# motoko_ice_dragon_v2.net
KiCad netlist of a schematic drawn in EAGLE
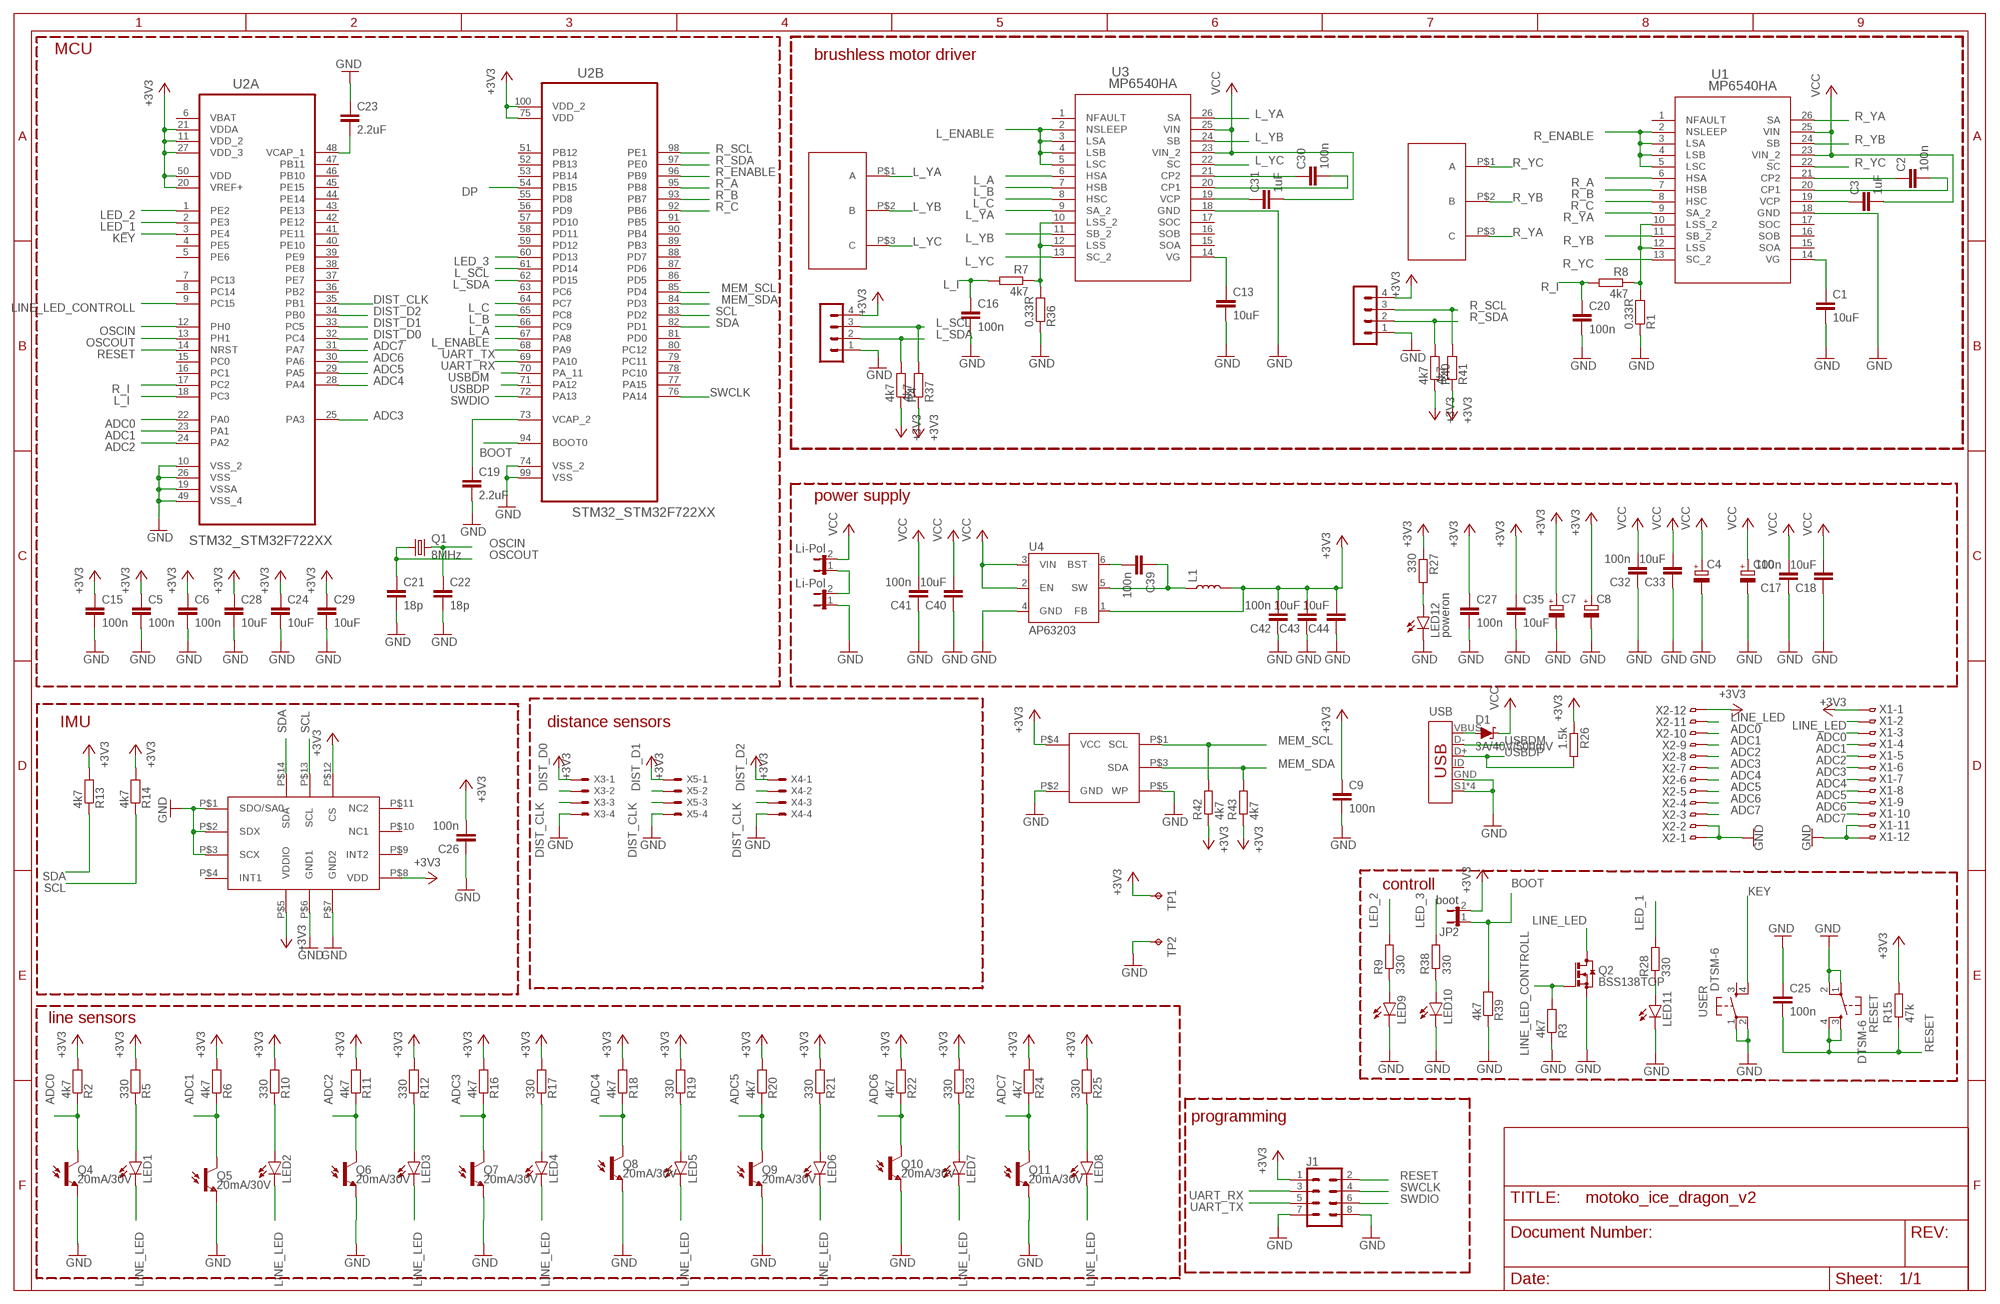
[diagram p0: schematic, sheet 1]

(export (version "E")
  (design (tool "Eeschema 10.0.6"))
  (components
    (comp (ref "C1")
      (value "10uF")
      (footprint "eagle-import:C0805")
      (libsource (lib "eagle-import") (part "C-EUC0805"))
    )
    (comp (ref "C2")
      (value "100n")
      (footprint "eagle-import:C0805")
      (libsource (lib "eagle-import") (part "C-EUC0805"))
    )
    (comp (ref "C3")
      (value "1uF")
      (footprint "eagle-import:C0805")
      (libsource (lib "eagle-import") (part "C-EUC0805"))
    )
    (comp (ref "C4")
      (value "CPOL-EU085CS-1AR")
      (footprint "eagle-import:085CS_1AR")
      (libsource (lib "eagle-import") (part "CPOL-EU085CS-1AR"))
    )
    (comp (ref "C5")
      (value "100n")
      (footprint "eagle-import:C0805")
      (libsource (lib "eagle-import") (part "C-EUC0805"))
    )
    (comp (ref "C6")
      (value "100n")
      (footprint "eagle-import:C0805")
      (libsource (lib "eagle-import") (part "C-EUC0805"))
    )
    (comp (ref "C7")
      (value "CPOL-EU085CS-1AR")
      (footprint "eagle-import:085CS_1AR")
      (libsource (lib "eagle-import") (part "CPOL-EU085CS-1AR"))
    )
    (comp (ref "C8")
      (value "CPOL-EU085CS-1AR")
      (footprint "eagle-import:085CS_1AR")
      (libsource (lib "eagle-import") (part "CPOL-EU085CS-1AR"))
    )
    (comp (ref "C9")
      (value "100n")
      (footprint "eagle-import:C0805")
      (libsource (lib "eagle-import") (part "C-EUC0805"))
    )
    (comp (ref "C10")
      (value "CPOL-EU085CS-1AR")
      (footprint "eagle-import:085CS_1AR")
      (libsource (lib "eagle-import") (part "CPOL-EU085CS-1AR"))
    )
    (comp (ref "C13")
      (value "10uF")
      (footprint "eagle-import:C0805")
      (libsource (lib "eagle-import") (part "C-EUC0805"))
    )
    (comp (ref "C15")
      (value "100n")
      (footprint "eagle-import:C0805")
      (libsource (lib "eagle-import") (part "C-EUC0805"))
    )
    (comp (ref "C16")
      (value "100n")
      (footprint "eagle-import:C0805")
      (libsource (lib "eagle-import") (part "C-EUC0805"))
    )
    (comp (ref "C17")
      (value "100n")
      (footprint "eagle-import:C0805")
      (libsource (lib "eagle-import") (part "C-EUC0805"))
    )
    (comp (ref "C18")
      (value "10uF")
      (footprint "eagle-import:C0805")
      (libsource (lib "eagle-import") (part "C-EUC0805"))
    )
    (comp (ref "C19")
      (value "2.2uF")
      (footprint "eagle-import:C0805")
      (libsource (lib "eagle-import") (part "C-EUC0805"))
    )
    (comp (ref "C20")
      (value "100n")
      (footprint "eagle-import:C0805")
      (libsource (lib "eagle-import") (part "C-EUC0805"))
    )
    (comp (ref "C21")
      (value "18p")
      (footprint "eagle-import:C0805")
      (libsource (lib "eagle-import") (part "C-EUC0805"))
    )
    (comp (ref "C22")
      (value "18p")
      (footprint "eagle-import:C0805")
      (libsource (lib "eagle-import") (part "C-EUC0805"))
    )
    (comp (ref "C23")
      (value "2.2uF")
      (footprint "eagle-import:C0805")
      (libsource (lib "eagle-import") (part "C-EUC0805"))
    )
    (comp (ref "C24")
      (value "10uF")
      (footprint "eagle-import:C0805")
      (libsource (lib "eagle-import") (part "C-EUC0805"))
    )
    (comp (ref "C25")
      (value "100n")
      (footprint "eagle-import:C0805")
      (libsource (lib "eagle-import") (part "C-EUC0805"))
    )
    (comp (ref "C26")
      (value "100n")
      (footprint "eagle-import:C0805")
      (libsource (lib "eagle-import") (part "C-EUC0805"))
    )
    (comp (ref "C27")
      (value "100n")
      (footprint "eagle-import:C0805")
      (libsource (lib "eagle-import") (part "C-EUC0805"))
    )
    (comp (ref "C28")
      (value "10uF")
      (footprint "eagle-import:C0805")
      (libsource (lib "eagle-import") (part "C-EUC0805"))
    )
    (comp (ref "C29")
      (value "10uF")
      (footprint "eagle-import:C0805")
      (libsource (lib "eagle-import") (part "C-EUC0805"))
    )
    (comp (ref "C30")
      (value "100n")
      (footprint "eagle-import:C0805")
      (libsource (lib "eagle-import") (part "C-EUC0805"))
    )
    (comp (ref "C31")
      (value "1uF")
      (footprint "eagle-import:C0805")
      (libsource (lib "eagle-import") (part "C-EUC0805"))
    )
    (comp (ref "C32")
      (value "100n")
      (footprint "eagle-import:C0805")
      (libsource (lib "eagle-import") (part "C-EUC0805"))
    )
    (comp (ref "C33")
      (value "10uF")
      (footprint "eagle-import:C0805")
      (libsource (lib "eagle-import") (part "C-EUC0805"))
    )
    (comp (ref "C35")
      (value "10uF")
      (footprint "eagle-import:C0805")
      (libsource (lib "eagle-import") (part "C-EUC0805"))
    )
    (comp (ref "C39")
      (value "100n")
      (footprint "eagle-import:C0805")
      (libsource (lib "eagle-import") (part "C-EUC0805"))
    )
    (comp (ref "C40")
      (value "10uF")
      (footprint "eagle-import:C0805")
      (libsource (lib "eagle-import") (part "C-EUC0805"))
    )
    (comp (ref "C41")
      (value "100n")
      (footprint "eagle-import:C0805")
      (libsource (lib "eagle-import") (part "C-EUC0805"))
    )
    (comp (ref "C42")
      (value "100n")
      (footprint "eagle-import:C0805")
      (libsource (lib "eagle-import") (part "C-EUC0805"))
    )
    (comp (ref "C43")
      (value "10uF")
      (footprint "eagle-import:C0805")
      (libsource (lib "eagle-import") (part "C-EUC0805"))
    )
    (comp (ref "C44")
      (value "10uF")
      (footprint "eagle-import:C0805")
      (libsource (lib "eagle-import") (part "C-EUC0805"))
    )
    (comp (ref "D1")
      (value "3A/40V/500mV")
      (footprint "eagle-import:SMA-DIODE")
      (libsource (lib "eagle-import") (part "DIODE-SCHOTTKY-B340A"))
    )
    (comp (ref "J1")
      (value "CONN_04X2")
      (footprint "eagle-import:2X4")
      (libsource (lib "eagle-import") (part "CONN_04X2"))
    )
    (comp (ref "JP1")
      (value "Li-Pol")
      (footprint "eagle-import:JP1")
      (libsource (lib "eagle-import") (part "JP1E"))
    )
    (comp (ref "JP2")
      (value "boot")
      (footprint "eagle-import:JP1")
      (libsource (lib "eagle-import") (part "JP1E"))
    )
    (comp (ref "JP3")
      (value "Li-Pol")
      (footprint "eagle-import:JP1")
      (libsource (lib "eagle-import") (part "JP1E"))
    )
    (comp (ref "L1")
      (value "4.7uH, TYS50204R7N-10")
      (footprint "eagle-import:CR54")
      (libsource (lib "eagle-import") (part "INDUCTOR-CR54-3.3UH"))
    )
    (comp (ref "LED1")
      (value "LEDCHIPLED_1206")
      (footprint "eagle-import:CHIPLED_1206")
      (libsource (lib "eagle-import") (part "LEDCHIPLED_1206"))
    )
    (comp (ref "LED2")
      (value "LEDCHIPLED_1206")
      (footprint "eagle-import:CHIPLED_1206")
      (libsource (lib "eagle-import") (part "LEDCHIPLED_1206"))
    )
    (comp (ref "LED3")
      (value "LEDCHIPLED_1206")
      (footprint "eagle-import:CHIPLED_1206")
      (libsource (lib "eagle-import") (part "LEDCHIPLED_1206"))
    )
    (comp (ref "LED4")
      (value "LEDCHIPLED_1206")
      (footprint "eagle-import:CHIPLED_1206")
      (libsource (lib "eagle-import") (part "LEDCHIPLED_1206"))
    )
    (comp (ref "LED5")
      (value "LEDCHIPLED_1206")
      (footprint "eagle-import:CHIPLED_1206")
      (libsource (lib "eagle-import") (part "LEDCHIPLED_1206"))
    )
    (comp (ref "LED6")
      (value "LEDCHIPLED_1206")
      (footprint "eagle-import:CHIPLED_1206")
      (libsource (lib "eagle-import") (part "LEDCHIPLED_1206"))
    )
    (comp (ref "LED7")
      (value "LEDCHIPLED_1206")
      (footprint "eagle-import:CHIPLED_1206")
      (libsource (lib "eagle-import") (part "LEDCHIPLED_1206"))
    )
    (comp (ref "LED8")
      (value "LEDCHIPLED_1206")
      (footprint "eagle-import:CHIPLED_1206")
      (libsource (lib "eagle-import") (part "LEDCHIPLED_1206"))
    )
    (comp (ref "LED9")
      (value "LEDCHIPLED_1206")
      (footprint "eagle-import:CHIPLED_1206")
      (libsource (lib "eagle-import") (part "LEDCHIPLED_1206"))
    )
    (comp (ref "LED10")
      (value "LEDCHIPLED_1206")
      (footprint "eagle-import:CHIPLED_1206")
      (libsource (lib "eagle-import") (part "LEDCHIPLED_1206"))
    )
    (comp (ref "LED11")
      (value "LEDCHIPLED_1206")
      (footprint "eagle-import:CHIPLED_1206")
      (libsource (lib "eagle-import") (part "LEDCHIPLED_1206"))
    )
    (comp (ref "LED12")
      (value "poweron")
      (footprint "eagle-import:CHIPLED_1206")
      (libsource (lib "eagle-import") (part "LEDCHIPLED_1206"))
    )
    (comp (ref "L_ENCODER")
      (value "MA04-1")
      (footprint "eagle-import:MA04-1")
      (libsource (lib "eagle-import") (part "MA04-1"))
    )
    (comp (ref "L_ENCODER1")
      (value "MA04-1")
      (footprint "eagle-import:MA04-1")
      (libsource (lib "eagle-import") (part "MA04-1"))
    )
    (comp (ref "Q1")
      (value "8MHz")
      (footprint "eagle-import:CTS406")
      (libsource (lib "eagle-import") (part "CRYSTALCTS406"))
    )
    (comp (ref "Q2")
      (value "BSS138TOP")
      (footprint "eagle-import:SOT23")
      (libsource (lib "eagle-import") (part "BSS138TOP"))
    )
    (comp (ref "Q4")
      (value "20mA/30V")
      (footprint "eagle-import:PT17-21C-L41-TR8")
      (libsource (lib "eagle-import") (part "PHOTOTRANSISTORPT17-21C-L41-TR8"))
    )
    (comp (ref "Q5")
      (value "20mA/30V")
      (footprint "eagle-import:PT17-21C-L41-TR8")
      (libsource (lib "eagle-import") (part "PHOTOTRANSISTORPT17-21C-L41-TR8"))
    )
    (comp (ref "Q6")
      (value "20mA/30V")
      (footprint "eagle-import:PT17-21C-L41-TR8")
      (libsource (lib "eagle-import") (part "PHOTOTRANSISTORPT17-21C-L41-TR8"))
    )
    (comp (ref "Q7")
      (value "20mA/30V")
      (footprint "eagle-import:PT17-21C-L41-TR8")
      (libsource (lib "eagle-import") (part "PHOTOTRANSISTORPT17-21C-L41-TR8"))
    )
    (comp (ref "Q8")
      (value "20mA/30V")
      (footprint "eagle-import:PT17-21C-L41-TR8")
      (libsource (lib "eagle-import") (part "PHOTOTRANSISTORPT17-21C-L41-TR8"))
    )
    (comp (ref "Q9")
      (value "20mA/30V")
      (footprint "eagle-import:PT17-21C-L41-TR8")
      (libsource (lib "eagle-import") (part "PHOTOTRANSISTORPT17-21C-L41-TR8"))
    )
    (comp (ref "Q10")
      (value "20mA/30V")
      (footprint "eagle-import:PT17-21C-L41-TR8")
      (libsource (lib "eagle-import") (part "PHOTOTRANSISTORPT17-21C-L41-TR8"))
    )
    (comp (ref "Q11")
      (value "20mA/30V")
      (footprint "eagle-import:PT17-21C-L41-TR8")
      (libsource (lib "eagle-import") (part "PHOTOTRANSISTORPT17-21C-L41-TR8"))
    )
    (comp (ref "R1")
      (value "0.33R")
      (footprint "eagle-import:M1206")
      (libsource (lib "eagle-import") (part "R-EU_M1206"))
    )
    (comp (ref "R2")
      (value "4k7")
      (footprint "eagle-import:M0805")
      (libsource (lib "eagle-import") (part "resistor_348_R-EU_M0805"))
    )
    (comp (ref "R3")
      (value "4k7")
      (footprint "eagle-import:M0805")
      (libsource (lib "eagle-import") (part "resistor_348_R-EU_M0805"))
    )
    (comp (ref "R4")
      (value "4k7")
      (footprint "eagle-import:M0805")
      (libsource (lib "eagle-import") (part "resistor_348_R-EU_M0805"))
    )
    (comp (ref "R5")
      (value "330")
      (footprint "eagle-import:M0805")
      (libsource (lib "eagle-import") (part "resistor_348_R-EU_M0805"))
    )
    (comp (ref "R6")
      (value "4k7")
      (footprint "eagle-import:M0805")
      (libsource (lib "eagle-import") (part "resistor_348_R-EU_M0805"))
    )
    (comp (ref "R7")
      (value "4k7")
      (footprint "eagle-import:M0805")
      (libsource (lib "eagle-import") (part "resistor_348_R-EU_M0805"))
    )
    (comp (ref "R8")
      (value "4k7")
      (footprint "eagle-import:M0805")
      (libsource (lib "eagle-import") (part "resistor_348_R-EU_M0805"))
    )
    (comp (ref "R9")
      (value "330")
      (footprint "eagle-import:M0805")
      (libsource (lib "eagle-import") (part "resistor_348_R-EU_M0805"))
    )
    (comp (ref "R10")
      (value "330")
      (footprint "eagle-import:M0805")
      (libsource (lib "eagle-import") (part "resistor_348_R-EU_M0805"))
    )
    (comp (ref "R11")
      (value "4k7")
      (footprint "eagle-import:M0805")
      (libsource (lib "eagle-import") (part "resistor_348_R-EU_M0805"))
    )
    (comp (ref "R12")
      (value "330")
      (footprint "eagle-import:M0805")
      (libsource (lib "eagle-import") (part "resistor_348_R-EU_M0805"))
    )
    (comp (ref "R13")
      (value "4k7")
      (footprint "eagle-import:M0805")
      (libsource (lib "eagle-import") (part "resistor_348_R-EU_M0805"))
    )
    (comp (ref "R14")
      (value "4k7")
      (footprint "eagle-import:M0805")
      (libsource (lib "eagle-import") (part "resistor_348_R-EU_M0805"))
    )
    (comp (ref "R15")
      (value "47k")
      (footprint "eagle-import:M0805")
      (libsource (lib "eagle-import") (part "resistor_348_R-EU_M0805"))
    )
    (comp (ref "R16")
      (value "4k7")
      (footprint "eagle-import:M0805")
      (libsource (lib "eagle-import") (part "resistor_348_R-EU_M0805"))
    )
    (comp (ref "R17")
      (value "330")
      (footprint "eagle-import:M0805")
      (libsource (lib "eagle-import") (part "resistor_348_R-EU_M0805"))
    )
    (comp (ref "R18")
      (value "4k7")
      (footprint "eagle-import:M0805")
      (libsource (lib "eagle-import") (part "resistor_348_R-EU_M0805"))
    )
    (comp (ref "R19")
      (value "330")
      (footprint "eagle-import:M0805")
      (libsource (lib "eagle-import") (part "resistor_348_R-EU_M0805"))
    )
    (comp (ref "R20")
      (value "4k7")
      (footprint "eagle-import:M0805")
      (libsource (lib "eagle-import") (part "resistor_348_R-EU_M0805"))
    )
    (comp (ref "R21")
      (value "330")
      (footprint "eagle-import:M0805")
      (libsource (lib "eagle-import") (part "resistor_348_R-EU_M0805"))
    )
    (comp (ref "R22")
      (value "4k7")
      (footprint "eagle-import:M0805")
      (libsource (lib "eagle-import") (part "resistor_348_R-EU_M0805"))
    )
    (comp (ref "R23")
      (value "330")
      (footprint "eagle-import:M0805")
      (libsource (lib "eagle-import") (part "resistor_348_R-EU_M0805"))
    )
    (comp (ref "R24")
      (value "4k7")
      (footprint "eagle-import:M0805")
      (libsource (lib "eagle-import") (part "resistor_348_R-EU_M0805"))
    )
    (comp (ref "R25")
      (value "330")
      (footprint "eagle-import:M0805")
      (libsource (lib "eagle-import") (part "resistor_348_R-EU_M0805"))
    )
    (comp (ref "R26")
      (value "1.5k")
      (footprint "eagle-import:M0805")
      (libsource (lib "eagle-import") (part "resistor_348_R-EU_M0805"))
    )
    (comp (ref "R27")
      (value "330")
      (footprint "eagle-import:M0805")
      (libsource (lib "eagle-import") (part "resistor_348_R-EU_M0805"))
    )
    (comp (ref "R28")
      (value "330")
      (footprint "eagle-import:M0805")
      (libsource (lib "eagle-import") (part "resistor_348_R-EU_M0805"))
    )
    (comp (ref "R36")
      (value "0.33R")
      (footprint "eagle-import:M1206")
      (libsource (lib "eagle-import") (part "R-EU_M1206"))
    )
    (comp (ref "R37")
      (value "4k7")
      (footprint "eagle-import:M0805")
      (libsource (lib "eagle-import") (part "resistor_348_R-EU_M0805"))
    )
    (comp (ref "R38")
      (value "330")
      (footprint "eagle-import:M0805")
      (libsource (lib "eagle-import") (part "resistor_348_R-EU_M0805"))
    )
    (comp (ref "R39")
      (value "4k7")
      (footprint "eagle-import:M0805")
      (libsource (lib "eagle-import") (part "resistor_348_R-EU_M0805"))
    )
    (comp (ref "R40")
      (value "4k7")
      (footprint "eagle-import:M0805")
      (libsource (lib "eagle-import") (part "resistor_348_R-EU_M0805"))
    )
    (comp (ref "R41")
      (value "4k7")
      (footprint "eagle-import:M0805")
      (libsource (lib "eagle-import") (part "resistor_348_R-EU_M0805"))
    )
    (comp (ref "R42")
      (value "4k7")
      (footprint "eagle-import:M0805")
      (libsource (lib "eagle-import") (part "R-EU_M0805"))
    )
    (comp (ref "R43")
      (value "4k7")
      (footprint "eagle-import:M0805")
      (libsource (lib "eagle-import") (part "R-EU_M0805"))
    )
    (comp (ref "RESET")
      (value "DTSM-6")
      (footprint "eagle-import:DTSM-6")
      (libsource (lib "eagle-import") (part "DTSM-6"))
    )
    (comp (ref "TP1")
      (value "TPB1,27")
      (footprint "eagle-import:B1,27")
      (libsource (lib "eagle-import") (part "TPB1,27"))
    )
    (comp (ref "TP2")
      (value "TPB1,27")
      (footprint "eagle-import:B1,27")
      (libsource (lib "eagle-import") (part "TPB1,27"))
    )
    (comp (ref "U$1")
      (value "BRUSHLESS_GIMBAL_MOTOR_WHEEL")
      (footprint "eagle-import:BRUSHLESS_GIMBAL_MOTOR_WHEEL")
      (libsource (lib "eagle-import") (part "BRUSHLESS_GIMBAL_MOTOR_WHEEL"))
    )
    (comp (ref "U$2")
      (value "BRUSHLESS_GIMBAL_MOTOR_WHEEL")
      (footprint "eagle-import:BRUSHLESS_GIMBAL_MOTOR_WHEEL")
      (libsource (lib "eagle-import") (part "BRUSHLESS_GIMBAL_MOTOR_WHEEL"))
    )
    (comp (ref "U$3")
      (value "LSM6DSM")
      (footprint "eagle-import:LGA14L")
      (libsource (lib "eagle-import") (part "LSM6DSM"))
    )
    (comp (ref "U$4")
      (value "24LC24_SOT23")
      (footprint "eagle-import:SOT23")
      (libsource (lib "eagle-import") (part "24LC24_SOT23"))
    )
    (comp (ref "U1")
      (value "MP6540HA")
      (footprint "eagle-import:QFN-5X5_MP6540HA_MNP")
      (fields (field (name "COPYRIGHT") "Copyright (C) 2018 Accelerated Designs. All rights reserved"))
      (libsource (lib "eagle-import") (part "MP6540HA"))
    )
    (comp (ref "U2")
      (value "STM32_STM32F722XX")
      (footprint "eagle-import:STM32_QFP50P1600X1600X160-100N")
      (fields (field (name "MPN") "STM32F407VET6"))
      (libsource (lib "eagle-import") (part "STM32_STM32F722XX"))
    )
    (comp (ref "U3")
      (value "MP6540HA")
      (footprint "eagle-import:QFN-5X5_MP6540HA_MNP")
      (fields (field (name "COPYRIGHT") "Copyright (C) 2018 Accelerated Designs. All rights reserved"))
      (libsource (lib "eagle-import") (part "MP6540HA"))
    )
    (comp (ref "U4")
      (value "AP63203")
      (footprint "eagle-import:SOT23-6")
      (libsource (lib "eagle-import") (part "AP63203"))
    )
    (comp (ref "USB")
      (value "USB_MINI-B_SMT")
      (footprint "eagle-import:USB-MINIB")
      (libsource (lib "eagle-import") (part "USB_MINI-B_SMT"))
    )
    (comp (ref "USER")
      (value "DTSM-6")
      (footprint "eagle-import:DTSM-6")
      (libsource (lib "eagle-import") (part "DTSM-6"))
    )
    (comp (ref "X1")
      (value "FH12-12S-0.5SH")
      (footprint "eagle-import:FH12-12S-0.5SH")
      (fields (field (name "MPN") "FH12-12S-0.5SH(55)"))
      (libsource (lib "eagle-import") (part "FH12-12S-0.5SH"))
    )
    (comp (ref "X2")
      (value "FH12-12S-0.5SH")
      (footprint "eagle-import:FH12-12S-0.5SH")
      (fields (field (name "MPN") "FH12-12S-0.5SH(55)"))
      (libsource (lib "eagle-import") (part "FH12-12S-0.5SH"))
    )
    (comp (ref "X3")
      (value "52745-0490")
      (footprint "eagle-import:52745-0490")
      (fields (field (name "MF") "MOLEX"))
      (libsource (lib "eagle-import") (part "52745-0490"))
    )
    (comp (ref "X4")
      (value "52745-0490")
      (footprint "eagle-import:52745-0490")
      (fields (field (name "MF") "MOLEX"))
      (libsource (lib "eagle-import") (part "52745-0490"))
    )
    (comp (ref "X5")
      (value "52745-0490")
      (footprint "eagle-import:52745-0490")
      (fields (field (name "MF") "MOLEX"))
      (libsource (lib "eagle-import") (part "52745-0490"))
    )
  )
  (nets
    (net (code "1") (name "+3V3") (class "Default")
      (node (ref "C15") (pin "1") (pinfunction "1_1") (pintype "passive"))
      (node (ref "C24") (pin "1") (pinfunction "1_1") (pintype "passive"))
      (node (ref "C26") (pin "2") (pinfunction "2_2") (pintype "passive"))
      (node (ref "C27") (pin "1") (pinfunction "1_1") (pintype "passive"))
      (node (ref "C28") (pin "1") (pinfunction "1_1") (pintype "passive"))
      (node (ref "C29") (pin "1") (pinfunction "1_1") (pintype "passive"))
      (node (ref "C35") (pin "1") (pinfunction "1_1") (pintype "passive"))
      (node (ref "C42") (pin "2") (pinfunction "2_2") (pintype "passive"))
      (node (ref "C43") (pin "2") (pinfunction "2_2") (pintype "passive"))
      (node (ref "C44") (pin "2") (pinfunction "2_2") (pintype "passive"))
      (node (ref "C5") (pin "1") (pinfunction "1_1") (pintype "passive"))
      (node (ref "C6") (pin "1") (pinfunction "1_1") (pintype "passive"))
      (node (ref "C7") (pin "+") (pinfunction "+_+") (pintype "passive"))
      (node (ref "C8") (pin "+") (pinfunction "+_+") (pintype "passive"))
      (node (ref "C9") (pin "1") (pinfunction "1_1") (pintype "passive"))
      (node (ref "J1") (pin "1") (pinfunction "1_1") (pintype "passive"))
      (node (ref "JP2") (pin "2") (pinfunction "2_2") (pintype "passive"))
      (node (ref "L1") (pin "P$2") (pinfunction "2_P$2") (pintype "passive"))
      (node (ref "L_ENCODER") (pin "4") (pinfunction "4_4") (pintype "passive"))
      (node (ref "L_ENCODER1") (pin "4") (pinfunction "4_4") (pintype "passive"))
      (node (ref "R10") (pin "2") (pinfunction "2_2") (pintype "passive"))
      (node (ref "R11") (pin "2") (pinfunction "2_2") (pintype "passive"))
      (node (ref "R12") (pin "2") (pinfunction "2_2") (pintype "passive"))
      (node (ref "R13") (pin "2") (pinfunction "2_2") (pintype "passive"))
      (node (ref "R14") (pin "2") (pinfunction "2_2") (pintype "passive"))
      (node (ref "R15") (pin "2") (pinfunction "2_2") (pintype "passive"))
      (node (ref "R16") (pin "2") (pinfunction "2_2") (pintype "passive"))
      (node (ref "R17") (pin "2") (pinfunction "2_2") (pintype "passive"))
      (node (ref "R18") (pin "2") (pinfunction "2_2") (pintype "passive"))
      (node (ref "R19") (pin "2") (pinfunction "2_2") (pintype "passive"))
      (node (ref "R2") (pin "2") (pinfunction "2_2") (pintype "passive"))
      (node (ref "R20") (pin "2") (pinfunction "2_2") (pintype "passive"))
      (node (ref "R21") (pin "2") (pinfunction "2_2") (pintype "passive"))
      (node (ref "R22") (pin "2") (pinfunction "2_2") (pintype "passive"))
      (node (ref "R23") (pin "2") (pinfunction "2_2") (pintype "passive"))
      (node (ref "R24") (pin "2") (pinfunction "2_2") (pintype "passive"))
      (node (ref "R25") (pin "2") (pinfunction "2_2") (pintype "passive"))
      (node (ref "R26") (pin "1") (pinfunction "1_1") (pintype "passive"))
      (node (ref "R27") (pin "1") (pinfunction "1_1") (pintype "passive"))
      (node (ref "R37") (pin "1") (pinfunction "1_1") (pintype "passive"))
      (node (ref "R4") (pin "1") (pinfunction "1_1") (pintype "passive"))
      (node (ref "R40") (pin "1") (pinfunction "1_1") (pintype "passive"))
      (node (ref "R41") (pin "1") (pinfunction "1_1") (pintype "passive"))
      (node (ref "R42") (pin "1") (pinfunction "1_1") (pintype "passive"))
      (node (ref "R43") (pin "1") (pinfunction "1_1") (pintype "passive"))
      (node (ref "R5") (pin "2") (pinfunction "2_2") (pintype "passive"))
      (node (ref "R6") (pin "2") (pinfunction "2_2") (pintype "passive"))
      (node (ref "TP1") (pin "TP") (pinfunction "TP_TP") (pintype "input"))
      (node (ref "U$3") (pin "P$12") (pinfunction "CS_P$12") (pintype "bidirectional"))
      (node (ref "U$3") (pin "P$5") (pinfunction "VDDIO_P$5") (pintype "bidirectional"))
      (node (ref "U$3") (pin "P$8") (pinfunction "VDD_P$8") (pintype "bidirectional"))
      (node (ref "U$4") (pin "P$4") (pinfunction "VCC_P$4") (pintype "bidirectional"))
      (node (ref "U2") (pin "100") (pinfunction "VDD_2_100") (pintype "power_in"))
      (node (ref "U2") (pin "11") (pinfunction "VDD_2_11") (pintype "power_in"))
      (node (ref "U2") (pin "20") (pinfunction "VREF+_20") (pintype "power_in"))
      (node (ref "U2") (pin "21") (pinfunction "VDDA_21") (pintype "power_in"))
      (node (ref "U2") (pin "27") (pinfunction "VDD_3_27") (pintype "power_in"))
      (node (ref "U2") (pin "50") (pinfunction "VDD_50") (pintype "power_in"))
      (node (ref "U2") (pin "75") (pinfunction "VDD_75") (pintype "power_in"))
      (node (ref "U4") (pin "1") (pinfunction "FB_1") (pintype "bidirectional"))
      (node (ref "X1") (pin "1") (pinfunction "1_1") (pintype "passive"))
      (node (ref "X2") (pin "12") (pinfunction "1_12") (pintype "passive"))
      (node (ref "X3") (pin "1") (pinfunction "S_1") (pintype "passive"))
      (node (ref "X4") (pin "1") (pinfunction "S_1") (pintype "passive"))
      (node (ref "X5") (pin "1") (pinfunction "S_1") (pintype "passive"))
    )
    (net (code "2") (name "/ADC0") (class "Default")
      (node (ref "Q4") (pin "C") (pinfunction "C_C") (pintype "passive"))
      (node (ref "R2") (pin "1") (pinfunction "1_1") (pintype "passive"))
      (node (ref "U2") (pin "22") (pinfunction "PA0_22") (pintype "bidirectional"))
      (node (ref "X1") (pin "3") (pinfunction "1_3") (pintype "passive"))
      (node (ref "X2") (pin "10") (pinfunction "1_10") (pintype "passive"))
    )
    (net (code "3") (name "/ADC1") (class "Default")
      (node (ref "Q5") (pin "C") (pinfunction "C_C") (pintype "passive"))
      (node (ref "R6") (pin "1") (pinfunction "1_1") (pintype "passive"))
      (node (ref "U2") (pin "23") (pinfunction "PA1_23") (pintype "bidirectional"))
      (node (ref "X1") (pin "4") (pinfunction "1_4") (pintype "passive"))
      (node (ref "X2") (pin "9") (pinfunction "1_9") (pintype "passive"))
    )
    (net (code "4") (name "/ADC2") (class "Default")
      (node (ref "Q6") (pin "C") (pinfunction "C_C") (pintype "passive"))
      (node (ref "R11") (pin "1") (pinfunction "1_1") (pintype "passive"))
      (node (ref "U2") (pin "24") (pinfunction "PA2_24") (pintype "bidirectional"))
      (node (ref "X1") (pin "5") (pinfunction "1_5") (pintype "passive"))
      (node (ref "X2") (pin "8") (pinfunction "1_8") (pintype "passive"))
    )
    (net (code "5") (name "/ADC3") (class "Default")
      (node (ref "Q7") (pin "C") (pinfunction "C_C") (pintype "passive"))
      (node (ref "R16") (pin "1") (pinfunction "1_1") (pintype "passive"))
      (node (ref "U2") (pin "25") (pinfunction "PA3_25") (pintype "bidirectional"))
      (node (ref "X1") (pin "6") (pinfunction "1_6") (pintype "passive"))
      (node (ref "X2") (pin "7") (pinfunction "1_7") (pintype "passive"))
    )
    (net (code "6") (name "/ADC4") (class "Default")
      (node (ref "Q8") (pin "C") (pinfunction "C_C") (pintype "passive"))
      (node (ref "R18") (pin "1") (pinfunction "1_1") (pintype "passive"))
      (node (ref "U2") (pin "28") (pinfunction "PA4_28") (pintype "bidirectional"))
      (node (ref "X1") (pin "7") (pinfunction "1_7") (pintype "passive"))
      (node (ref "X2") (pin "6") (pinfunction "1_6") (pintype "passive"))
    )
    (net (code "7") (name "/ADC5") (class "Default")
      (node (ref "Q9") (pin "C") (pinfunction "C_C") (pintype "passive"))
      (node (ref "R20") (pin "1") (pinfunction "1_1") (pintype "passive"))
      (node (ref "U2") (pin "29") (pinfunction "PA5_29") (pintype "bidirectional"))
      (node (ref "X1") (pin "8") (pinfunction "1_8") (pintype "passive"))
      (node (ref "X2") (pin "5") (pinfunction "1_5") (pintype "passive"))
    )
    (net (code "8") (name "/ADC6") (class "Default")
      (node (ref "Q10") (pin "C") (pinfunction "C_C") (pintype "passive"))
      (node (ref "R22") (pin "1") (pinfunction "1_1") (pintype "passive"))
      (node (ref "U2") (pin "30") (pinfunction "PA6_30") (pintype "bidirectional"))
      (node (ref "X1") (pin "9") (pinfunction "1_9") (pintype "passive"))
      (node (ref "X2") (pin "4") (pinfunction "1_4") (pintype "passive"))
    )
    (net (code "9") (name "/ADC7") (class "Default")
      (node (ref "Q11") (pin "C") (pinfunction "C_C") (pintype "passive"))
      (node (ref "R24") (pin "1") (pinfunction "1_1") (pintype "passive"))
      (node (ref "U2") (pin "31") (pinfunction "PA7_31") (pintype "bidirectional"))
      (node (ref "X1") (pin "10") (pinfunction "1_10") (pintype "passive"))
      (node (ref "X2") (pin "3") (pinfunction "1_3") (pintype "passive"))
    )
    (net (code "10") (name "/BOOT") (class "Default")
      (node (ref "JP2") (pin "1") (pinfunction "1_1") (pintype "passive"))
      (node (ref "R39") (pin "2") (pinfunction "2_2") (pintype "passive"))
      (node (ref "U2") (pin "94") (pinfunction "BOOT0_94") (pintype "input"))
    )
    (net (code "11") (name "/DIST_CLK") (class "Default")
      (node (ref "U2") (pin "35") (pinfunction "PB1_35") (pintype "bidirectional"))
      (node (ref "X3") (pin "3") (pinfunction "S_3") (pintype "passive"))
      (node (ref "X4") (pin "3") (pinfunction "S_3") (pintype "passive"))
      (node (ref "X5") (pin "3") (pinfunction "S_3") (pintype "passive"))
    )
    (net (code "12") (name "/DIST_D0") (class "Default")
      (node (ref "U2") (pin "32") (pinfunction "PC4_32") (pintype "bidirectional"))
      (node (ref "X3") (pin "2") (pinfunction "S_2") (pintype "passive"))
    )
    (net (code "13") (name "/DIST_D1") (class "Default")
      (node (ref "U2") (pin "33") (pinfunction "PC5_33") (pintype "bidirectional"))
      (node (ref "X5") (pin "2") (pinfunction "S_2") (pintype "passive"))
    )
    (net (code "14") (name "/DIST_D2") (class "Default")
      (node (ref "U2") (pin "34") (pinfunction "PB0_34") (pintype "bidirectional"))
      (node (ref "X4") (pin "2") (pinfunction "S_2") (pintype "passive"))
    )
    (net (code "15") (name "/DP") (class "Default")
      (node (ref "U2") (pin "54") (pinfunction "PB15_54") (pintype "bidirectional"))
    )
    (net (code "16") (name "/KEY") (class "Default")
      (node (ref "U2") (pin "3") (pinfunction "PE4_3") (pintype "bidirectional"))
      (node (ref "USER") (pin "4") (pinfunction "4_4") (pintype "passive"))
    )
    (net (code "17") (name "/LED_1") (class "Default")
      (node (ref "R28") (pin "2") (pinfunction "2_2") (pintype "passive"))
      (node (ref "U2") (pin "2") (pinfunction "PE3_2") (pintype "bidirectional"))
    )
    (net (code "18") (name "/LED_2") (class "Default")
      (node (ref "R9") (pin "2") (pinfunction "2_2") (pintype "passive"))
      (node (ref "U2") (pin "1") (pinfunction "PE2_1") (pintype "bidirectional"))
    )
    (net (code "19") (name "/LED_3") (class "Default")
      (node (ref "R38") (pin "2") (pinfunction "2_2") (pintype "passive"))
      (node (ref "U2") (pin "60") (pinfunction "PD13_60") (pintype "bidirectional"))
    )
    (net (code "20") (name "/LINE_LED") (class "Default")
      (node (ref "LED1") (pin "C") (pinfunction "C_C") (pintype "passive"))
      (node (ref "LED2") (pin "C") (pinfunction "C_C") (pintype "passive"))
      (node (ref "LED3") (pin "C") (pinfunction "C_C") (pintype "passive"))
      (node (ref "LED4") (pin "C") (pinfunction "C_C") (pintype "passive"))
      (node (ref "LED5") (pin "C") (pinfunction "C_C") (pintype "passive"))
      (node (ref "LED6") (pin "C") (pinfunction "C_C") (pintype "passive"))
      (node (ref "LED7") (pin "C") (pinfunction "C_C") (pintype "passive"))
      (node (ref "LED8") (pin "C") (pinfunction "C_C") (pintype "passive"))
      (node (ref "Q2") (pin "3") (pinfunction "D_3") (pintype "passive"))
      (node (ref "X1") (pin "2") (pinfunction "1_2") (pintype "passive"))
      (node (ref "X2") (pin "11") (pinfunction "1_11") (pintype "passive"))
    )
    (net (code "21") (name "/LINE_LED_CONTROLL") (class "Default")
      (node (ref "Q2") (pin "1") (pinfunction "G_1") (pintype "passive"))
      (node (ref "R3") (pin "2") (pinfunction "2_2") (pintype "passive"))
      (node (ref "U2") (pin "9") (pinfunction "PC15_9") (pintype "bidirectional"))
    )
    (net (code "22") (name "/L_A") (class "Default")
      (node (ref "U2") (pin "66") (pinfunction "PC9_66") (pintype "bidirectional"))
      (node (ref "U3") (pin "6") (pinfunction "HSA_6") (pintype "passive"))
    )
    (net (code "23") (name "/L_B") (class "Default")
      (node (ref "U2") (pin "65") (pinfunction "PC8_65") (pintype "bidirectional"))
      (node (ref "U3") (pin "7") (pinfunction "HSB_7") (pintype "passive"))
    )
    (net (code "24") (name "/L_C") (class "Default")
      (node (ref "U2") (pin "64") (pinfunction "PC7_64") (pintype "bidirectional"))
      (node (ref "U3") (pin "8") (pinfunction "HSC_8") (pintype "passive"))
    )
    (net (code "25") (name "/L_ENABLE") (class "Default")
      (node (ref "U2") (pin "67") (pinfunction "PA8_67") (pintype "bidirectional"))
      (node (ref "U3") (pin "2") (pinfunction "NSLEEP_2") (pintype "input"))
      (node (ref "U3") (pin "3") (pinfunction "LSA_3") (pintype "passive"))
      (node (ref "U3") (pin "4") (pinfunction "LSB_4") (pintype "passive"))
      (node (ref "U3") (pin "5") (pinfunction "LSC_5") (pintype "passive"))
    )
    (net (code "26") (name "/L_I") (class "Default")
      (node (ref "C16") (pin "1") (pinfunction "1_1") (pintype "passive"))
      (node (ref "R7") (pin "2") (pinfunction "2_2") (pintype "passive"))
      (node (ref "U2") (pin "18") (pinfunction "PC3_18") (pintype "bidirectional"))
    )
    (net (code "27") (name "/L_SCL") (class "Default")
      (node (ref "L_ENCODER") (pin "3") (pinfunction "3_3") (pintype "passive"))
      (node (ref "R37") (pin "2") (pinfunction "2_2") (pintype "passive"))
      (node (ref "U2") (pin "61") (pinfunction "PD14_61") (pintype "bidirectional"))
    )
    (net (code "28") (name "/L_SDA") (class "Default")
      (node (ref "L_ENCODER") (pin "2") (pinfunction "2_2") (pintype "passive"))
      (node (ref "R4") (pin "2") (pinfunction "2_2") (pintype "passive"))
      (node (ref "U2") (pin "62") (pinfunction "PD15_62") (pintype "bidirectional"))
    )
    (net (code "29") (name "/L_YA") (class "Default")
      (node (ref "U$1") (pin "P$1") (pinfunction "A_P$1") (pintype "input"))
      (node (ref "U3") (pin "26") (pinfunction "SA_26") (pintype "output"))
      (node (ref "U3") (pin "9") (pinfunction "SA_2_9") (pintype "output"))
    )
    (net (code "30") (name "/L_YB") (class "Default")
      (node (ref "U$1") (pin "P$2") (pinfunction "B_P$2") (pintype "input"))
      (node (ref "U3") (pin "11") (pinfunction "SB_2_11") (pintype "output"))
      (node (ref "U3") (pin "24") (pinfunction "SB_24") (pintype "output"))
    )
    (net (code "31") (name "/L_YC") (class "Default")
      (node (ref "U$1") (pin "P$3") (pinfunction "C_P$3") (pintype "input"))
      (node (ref "U3") (pin "13") (pinfunction "SC_2_13") (pintype "output"))
      (node (ref "U3") (pin "22") (pinfunction "SC_22") (pintype "output"))
    )
    (net (code "32") (name "/MEM_SCL") (class "Default")
      (node (ref "R42") (pin "2") (pinfunction "2_2") (pintype "passive"))
      (node (ref "U$4") (pin "P$1") (pinfunction "SCL_P$1") (pintype "bidirectional"))
      (node (ref "U2") (pin "85") (pinfunction "PD4_85") (pintype "bidirectional"))
    )
    (net (code "33") (name "/MEM_SDA") (class "Default")
      (node (ref "R43") (pin "2") (pinfunction "2_2") (pintype "passive"))
      (node (ref "U$4") (pin "P$3") (pinfunction "SDA_P$3") (pintype "bidirectional"))
      (node (ref "U2") (pin "84") (pinfunction "PD3_84") (pintype "bidirectional"))
    )
    (net (code "34") (name "/OSCIN") (class "Default")
      (node (ref "C22") (pin "1") (pinfunction "1_1") (pintype "passive"))
      (node (ref "Q1") (pin "3") (pinfunction "2_3") (pintype "passive"))
      (node (ref "U2") (pin "12") (pinfunction "PH0_12") (pintype "bidirectional"))
    )
    (net (code "35") (name "/OSCOUT") (class "Default")
      (node (ref "C21") (pin "1") (pinfunction "1_1") (pintype "passive"))
      (node (ref "Q1") (pin "1") (pinfunction "1_1") (pintype "passive"))
      (node (ref "U2") (pin "13") (pinfunction "PH1_13") (pintype "bidirectional"))
    )
    (net (code "36") (name "/RESET") (class "Default")
      (node (ref "C25") (pin "2") (pinfunction "2_2") (pintype "passive"))
      (node (ref "J1") (pin "2") (pinfunction "2_2") (pintype "passive"))
      (node (ref "R15") (pin "1") (pinfunction "1_1") (pintype "passive"))
      (node (ref "RESET") (pin "3") (pinfunction "3_3") (pintype "passive"))
      (node (ref "RESET") (pin "4") (pinfunction "4_4") (pintype "passive"))
      (node (ref "U2") (pin "14") (pinfunction "NRST_14") (pintype "bidirectional"))
    )
    (net (code "37") (name "/R_A") (class "Default")
      (node (ref "U1") (pin "6") (pinfunction "HSA_6") (pintype "passive"))
      (node (ref "U2") (pin "95") (pinfunction "PB8_95") (pintype "bidirectional"))
    )
    (net (code "38") (name "/R_B") (class "Default")
      (node (ref "U1") (pin "7") (pinfunction "HSB_7") (pintype "passive"))
      (node (ref "U2") (pin "93") (pinfunction "PB7_93") (pintype "bidirectional"))
    )
    (net (code "39") (name "/R_C") (class "Default")
      (node (ref "U1") (pin "8") (pinfunction "HSC_8") (pintype "passive"))
      (node (ref "U2") (pin "92") (pinfunction "PB6_92") (pintype "bidirectional"))
    )
    (net (code "40") (name "/R_ENABLE") (class "Default")
      (node (ref "U1") (pin "2") (pinfunction "NSLEEP_2") (pintype "input"))
      (node (ref "U1") (pin "3") (pinfunction "LSA_3") (pintype "passive"))
      (node (ref "U1") (pin "4") (pinfunction "LSB_4") (pintype "passive"))
      (node (ref "U1") (pin "5") (pinfunction "LSC_5") (pintype "passive"))
      (node (ref "U2") (pin "96") (pinfunction "PB9_96") (pintype "bidirectional"))
    )
    (net (code "41") (name "/R_I") (class "Default")
      (node (ref "C20") (pin "1") (pinfunction "1_1") (pintype "passive"))
      (node (ref "R8") (pin "2") (pinfunction "2_2") (pintype "passive"))
      (node (ref "U2") (pin "17") (pinfunction "PC2_17") (pintype "bidirectional"))
    )
    (net (code "42") (name "/R_SCL") (class "Default")
      (node (ref "L_ENCODER1") (pin "3") (pinfunction "3_3") (pintype "passive"))
      (node (ref "R41") (pin "2") (pinfunction "2_2") (pintype "passive"))
      (node (ref "U2") (pin "98") (pinfunction "PE1_98") (pintype "bidirectional"))
    )
    (net (code "43") (name "/R_SDA") (class "Default")
      (node (ref "L_ENCODER1") (pin "2") (pinfunction "2_2") (pintype "passive"))
      (node (ref "R40") (pin "2") (pinfunction "2_2") (pintype "passive"))
      (node (ref "U2") (pin "97") (pinfunction "PE0_97") (pintype "bidirectional"))
    )
    (net (code "44") (name "/R_YA") (class "Default")
      (node (ref "U$2") (pin "P$3") (pinfunction "C_P$3") (pintype "input"))
      (node (ref "U1") (pin "26") (pinfunction "SA_26") (pintype "output"))
      (node (ref "U1") (pin "9") (pinfunction "SA_2_9") (pintype "output"))
    )
    (net (code "45") (name "/R_YB") (class "Default")
      (node (ref "U$2") (pin "P$2") (pinfunction "B_P$2") (pintype "input"))
      (node (ref "U1") (pin "11") (pinfunction "SB_2_11") (pintype "output"))
      (node (ref "U1") (pin "24") (pinfunction "SB_24") (pintype "output"))
    )
    (net (code "46") (name "/R_YC") (class "Default")
      (node (ref "U$2") (pin "P$1") (pinfunction "A_P$1") (pintype "input"))
      (node (ref "U1") (pin "13") (pinfunction "SC_2_13") (pintype "output"))
      (node (ref "U1") (pin "22") (pinfunction "SC_22") (pintype "output"))
    )
    (net (code "47") (name "/SCL") (class "Default")
      (node (ref "R14") (pin "1") (pinfunction "1_1") (pintype "passive"))
      (node (ref "U$3") (pin "P$13") (pinfunction "SCL_P$13") (pintype "bidirectional"))
      (node (ref "U2") (pin "83") (pinfunction "PD2_83") (pintype "bidirectional"))
    )
    (net (code "48") (name "/SDA") (class "Default")
      (node (ref "R13") (pin "1") (pinfunction "1_1") (pintype "passive"))
      (node (ref "U$3") (pin "P$14") (pinfunction "SDA_P$14") (pintype "bidirectional"))
      (node (ref "U2") (pin "82") (pinfunction "PD1_82") (pintype "bidirectional"))
    )
    (net (code "49") (name "/SWCLK") (class "Default")
      (node (ref "J1") (pin "4") (pinfunction "4_4") (pintype "passive"))
      (node (ref "U2") (pin "76") (pinfunction "PA14_76") (pintype "bidirectional"))
    )
    (net (code "50") (name "/SWDIO") (class "Default")
      (node (ref "J1") (pin "6") (pinfunction "6_6") (pintype "passive"))
      (node (ref "U2") (pin "72") (pinfunction "PA13_72") (pintype "bidirectional"))
    )
    (net (code "51") (name "/UART_RX") (class "Default")
      (node (ref "J1") (pin "3") (pinfunction "3_3") (pintype "passive"))
      (node (ref "U2") (pin "69") (pinfunction "PA10_69") (pintype "bidirectional"))
    )
    (net (code "52") (name "/UART_TX") (class "Default")
      (node (ref "J1") (pin "5") (pinfunction "5_5") (pintype "passive"))
      (node (ref "U2") (pin "68") (pinfunction "PA9_68") (pintype "bidirectional"))
    )
    (net (code "53") (name "/USBDM") (class "Default")
      (node (ref "U2") (pin "70") (pinfunction "PA_11_70") (pintype "bidirectional"))
      (node (ref "USB") (pin "D-") (pinfunction "D-_D-") (pintype "bidirectional"))
    )
    (net (code "54") (name "/USBDP") (class "Default")
      (node (ref "R26") (pin "2") (pinfunction "2_2") (pintype "passive"))
      (node (ref "U2") (pin "71") (pinfunction "PA12_71") (pintype "bidirectional"))
      (node (ref "USB") (pin "D+") (pinfunction "D+_D+") (pintype "bidirectional"))
    )
    (net (code "55") (name "/VBAT") (class "Default")
      (node (ref "U2") (pin "6") (pinfunction "VBAT_6") (pintype "power_in"))
    )
    (net (code "56") (name "GND") (class "Default")
      (node (ref "C1") (pin "2") (pinfunction "2_2") (pintype "passive"))
      (node (ref "C10") (pin "-") (pinfunction "-_-") (pintype "passive"))
      (node (ref "C13") (pin "2") (pinfunction "2_2") (pintype "passive"))
      (node (ref "C15") (pin "2") (pinfunction "2_2") (pintype "passive"))
      (node (ref "C16") (pin "2") (pinfunction "2_2") (pintype "passive"))
      (node (ref "C17") (pin "1") (pinfunction "1_1") (pintype "passive"))
      (node (ref "C18") (pin "1") (pinfunction "1_1") (pintype "passive"))
      (node (ref "C19") (pin "2") (pinfunction "2_2") (pintype "passive"))
      (node (ref "C20") (pin "2") (pinfunction "2_2") (pintype "passive"))
      (node (ref "C21") (pin "2") (pinfunction "2_2") (pintype "passive"))
      (node (ref "C22") (pin "2") (pinfunction "2_2") (pintype "passive"))
      (node (ref "C23") (pin "1") (pinfunction "1_1") (pintype "passive"))
      (node (ref "C24") (pin "2") (pinfunction "2_2") (pintype "passive"))
      (node (ref "C25") (pin "1") (pinfunction "1_1") (pintype "passive"))
      (node (ref "C26") (pin "1") (pinfunction "1_1") (pintype "passive"))
      (node (ref "C27") (pin "2") (pinfunction "2_2") (pintype "passive"))
      (node (ref "C28") (pin "2") (pinfunction "2_2") (pintype "passive"))
      (node (ref "C29") (pin "2") (pinfunction "2_2") (pintype "passive"))
      (node (ref "C32") (pin "1") (pinfunction "1_1") (pintype "passive"))
      (node (ref "C33") (pin "1") (pinfunction "1_1") (pintype "passive"))
      (node (ref "C35") (pin "2") (pinfunction "2_2") (pintype "passive"))
      (node (ref "C4") (pin "-") (pinfunction "-_-") (pintype "passive"))
      (node (ref "C40") (pin "1") (pinfunction "1_1") (pintype "passive"))
      (node (ref "C41") (pin "1") (pinfunction "1_1") (pintype "passive"))
      (node (ref "C42") (pin "1") (pinfunction "1_1") (pintype "passive"))
      (node (ref "C43") (pin "1") (pinfunction "1_1") (pintype "passive"))
      (node (ref "C44") (pin "1") (pinfunction "1_1") (pintype "passive"))
      (node (ref "C5") (pin "2") (pinfunction "2_2") (pintype "passive"))
      (node (ref "C6") (pin "2") (pinfunction "2_2") (pintype "passive"))
      (node (ref "C7") (pin "-") (pinfunction "-_-") (pintype "passive"))
      (node (ref "C8") (pin "-") (pinfunction "-_-") (pintype "passive"))
      (node (ref "C9") (pin "2") (pinfunction "2_2") (pintype "passive"))
      (node (ref "J1") (pin "7") (pinfunction "7_7") (pintype "passive"))
      (node (ref "J1") (pin "8") (pinfunction "8_8") (pintype "passive"))
      (node (ref "JP3") (pin "1") (pinfunction "1_1") (pintype "passive"))
      (node (ref "LED10") (pin "C") (pinfunction "C_C") (pintype "passive"))
      (node (ref "LED11") (pin "C") (pinfunction "C_C") (pintype "passive"))
      (node (ref "LED12") (pin "C") (pinfunction "C_C") (pintype "passive"))
      (node (ref "LED9") (pin "C") (pinfunction "C_C") (pintype "passive"))
      (node (ref "L_ENCODER") (pin "1") (pinfunction "1_1") (pintype "passive"))
      (node (ref "L_ENCODER1") (pin "1") (pinfunction "1_1") (pintype "passive"))
      (node (ref "Q10") (pin "E") (pinfunction "E_E") (pintype "passive"))
      (node (ref "Q11") (pin "E") (pinfunction "E_E") (pintype "passive"))
      (node (ref "Q2") (pin "2") (pinfunction "S_2") (pintype "passive"))
      (node (ref "Q4") (pin "E") (pinfunction "E_E") (pintype "passive"))
      (node (ref "Q5") (pin "E") (pinfunction "E_E") (pintype "passive"))
      (node (ref "Q6") (pin "E") (pinfunction "E_E") (pintype "passive"))
      (node (ref "Q7") (pin "E") (pinfunction "E_E") (pintype "passive"))
      (node (ref "Q8") (pin "E") (pinfunction "E_E") (pintype "passive"))
      (node (ref "Q9") (pin "E") (pinfunction "E_E") (pintype "passive"))
      (node (ref "R1") (pin "1") (pinfunction "1_1") (pintype "passive"))
      (node (ref "R3") (pin "1") (pinfunction "1_1") (pintype "passive"))
      (node (ref "R36") (pin "1") (pinfunction "1_1") (pintype "passive"))
      (node (ref "R39") (pin "1") (pinfunction "1_1") (pintype "passive"))
      (node (ref "RESET") (pin "1") (pinfunction "1_1") (pintype "passive"))
      (node (ref "RESET") (pin "2") (pinfunction "2_2") (pintype "passive"))
      (node (ref "TP2") (pin "TP") (pinfunction "TP_TP") (pintype "input"))
      (node (ref "U$3") (pin "P$1") (pinfunction "SDO/SA0_P$1") (pintype "bidirectional"))
      (node (ref "U$3") (pin "P$2") (pinfunction "SDX_P$2") (pintype "bidirectional"))
      (node (ref "U$3") (pin "P$3") (pinfunction "SCX_P$3") (pintype "bidirectional"))
      (node (ref "U$3") (pin "P$6") (pinfunction "GND1_P$6") (pintype "bidirectional"))
      (node (ref "U$3") (pin "P$7") (pinfunction "GND2_P$7") (pintype "bidirectional"))
      (node (ref "U$4") (pin "P$2") (pinfunction "GND_P$2") (pintype "bidirectional"))
      (node (ref "U$4") (pin "P$5") (pinfunction "WP_P$5") (pintype "bidirectional"))
      (node (ref "U1") (pin "18") (pinfunction "GND_18") (pintype "passive"))
      (node (ref "U2") (pin "10") (pinfunction "VSS_2_10") (pintype "passive"))
      (node (ref "U2") (pin "19") (pinfunction "VSSA_19") (pintype "passive"))
      (node (ref "U2") (pin "26") (pinfunction "VSS_26") (pintype "passive"))
      (node (ref "U2") (pin "49") (pinfunction "VSS_4_49") (pintype "power_in"))
      (node (ref "U2") (pin "74") (pinfunction "VSS_2_74") (pintype "passive"))
      (node (ref "U2") (pin "99") (pinfunction "VSS_99") (pintype "passive"))
      (node (ref "U3") (pin "18") (pinfunction "GND_18") (pintype "passive"))
      (node (ref "U4") (pin "4") (pinfunction "GND_4") (pintype "bidirectional"))
      (node (ref "USB") (pin "GND") (pinfunction "GND_GND") (pintype "power_in"))
      (node (ref "USB") (pin "S1") (pinfunction "SHIELD_S1") (pintype "bidirectional"))
      (node (ref "USB") (pin "S2") (pinfunction "SHIELD_S2") (pintype "bidirectional"))
      (node (ref "USB") (pin "S3") (pinfunction "SHIELD_S3") (pintype "bidirectional"))
      (node (ref "USB") (pin "S4") (pinfunction "SHIELD_S4") (pintype "bidirectional"))
      (node (ref "USER") (pin "1") (pinfunction "1_1") (pintype "passive"))
      (node (ref "USER") (pin "2") (pinfunction "2_2") (pintype "passive"))
      (node (ref "X1") (pin "11") (pinfunction "1_11") (pintype "passive"))
      (node (ref "X1") (pin "12") (pinfunction "1_12") (pintype "passive"))
      (node (ref "X2") (pin "1") (pinfunction "1_1") (pintype "passive"))
      (node (ref "X2") (pin "2") (pinfunction "1_2") (pintype "passive"))
      (node (ref "X3") (pin "4") (pinfunction "S_4") (pintype "passive"))
      (node (ref "X4") (pin "4") (pinfunction "S_4") (pintype "passive"))
      (node (ref "X5") (pin "4") (pinfunction "S_4") (pintype "passive"))
    )
    (net (code "57") (name "Net-(D1-PadA)") (class "Default")
      (node (ref "D1") (pin "A") (pinfunction "A_A") (pintype "passive"))
      (node (ref "USB") (pin "VBUS") (pinfunction "VBUS_VBUS") (pintype "power_in"))
    )
    (net (code "58") (name "Net-(JP1-Pad1)") (class "Default")
      (node (ref "JP1") (pin "1") (pinfunction "1_1") (pintype "passive"))
      (node (ref "JP3") (pin "2") (pinfunction "2_2") (pintype "passive"))
    )
    (net (code "59") (name "Net-(L1-1)") (class "Default")
      (node (ref "C39") (pin "1") (pinfunction "1_1") (pintype "passive"))
      (node (ref "L1") (pin "P$1") (pinfunction "1_P$1") (pintype "passive"))
      (node (ref "U4") (pin "5") (pinfunction "SW_5") (pintype "bidirectional"))
    )
    (net (code "60") (name "Net-(LED1-PadA)") (class "Default")
      (node (ref "LED1") (pin "A") (pinfunction "A_A") (pintype "passive"))
      (node (ref "R5") (pin "1") (pinfunction "1_1") (pintype "passive"))
    )
    (net (code "61") (name "Net-(LED2-PadA)") (class "Default")
      (node (ref "LED2") (pin "A") (pinfunction "A_A") (pintype "passive"))
      (node (ref "R10") (pin "1") (pinfunction "1_1") (pintype "passive"))
    )
    (net (code "62") (name "Net-(LED3-PadA)") (class "Default")
      (node (ref "LED3") (pin "A") (pinfunction "A_A") (pintype "passive"))
      (node (ref "R12") (pin "1") (pinfunction "1_1") (pintype "passive"))
    )
    (net (code "63") (name "Net-(LED4-PadA)") (class "Default")
      (node (ref "LED4") (pin "A") (pinfunction "A_A") (pintype "passive"))
      (node (ref "R17") (pin "1") (pinfunction "1_1") (pintype "passive"))
    )
    (net (code "64") (name "Net-(LED5-PadA)") (class "Default")
      (node (ref "LED5") (pin "A") (pinfunction "A_A") (pintype "passive"))
      (node (ref "R19") (pin "1") (pinfunction "1_1") (pintype "passive"))
    )
    (net (code "65") (name "Net-(LED6-PadA)") (class "Default")
      (node (ref "LED6") (pin "A") (pinfunction "A_A") (pintype "passive"))
      (node (ref "R21") (pin "1") (pinfunction "1_1") (pintype "passive"))
    )
    (net (code "66") (name "Net-(LED7-PadA)") (class "Default")
      (node (ref "LED7") (pin "A") (pinfunction "A_A") (pintype "passive"))
      (node (ref "R23") (pin "1") (pinfunction "1_1") (pintype "passive"))
    )
    (net (code "67") (name "Net-(LED8-PadA)") (class "Default")
      (node (ref "LED8") (pin "A") (pinfunction "A_A") (pintype "passive"))
      (node (ref "R25") (pin "1") (pinfunction "1_1") (pintype "passive"))
    )
    (net (code "68") (name "Net-(LED9-PadA)") (class "Default")
      (node (ref "LED9") (pin "A") (pinfunction "A_A") (pintype "passive"))
      (node (ref "R9") (pin "1") (pinfunction "1_1") (pintype "passive"))
    )
    (net (code "69") (name "Net-(LED10-PadA)") (class "Default")
      (node (ref "LED10") (pin "A") (pinfunction "A_A") (pintype "passive"))
      (node (ref "R38") (pin "1") (pinfunction "1_1") (pintype "passive"))
    )
    (net (code "70") (name "Net-(LED11-PadA)") (class "Default")
      (node (ref "LED11") (pin "A") (pinfunction "A_A") (pintype "passive"))
      (node (ref "R28") (pin "1") (pinfunction "1_1") (pintype "passive"))
    )
    (net (code "71") (name "Net-(LED12-PadA)") (class "Default")
      (node (ref "LED12") (pin "A") (pinfunction "A_A") (pintype "passive"))
      (node (ref "R27") (pin "2") (pinfunction "2_2") (pintype "passive"))
    )
    (net (code "72") (name "Net-(U1-CP1)") (class "Default")
      (node (ref "C2") (pin "2") (pinfunction "2_2") (pintype "passive"))
      (node (ref "U1") (pin "20") (pinfunction "CP1_20") (pintype "passive"))
    )
    (net (code "73") (name "Net-(U1-CP2)") (class "Default")
      (node (ref "C2") (pin "1") (pinfunction "1_1") (pintype "passive"))
      (node (ref "U1") (pin "21") (pinfunction "CP2_21") (pintype "passive"))
    )
    (net (code "74") (name "Net-(U1-LSS)") (class "Default")
      (node (ref "R1") (pin "2") (pinfunction "2_2") (pintype "passive"))
      (node (ref "R8") (pin "1") (pinfunction "1_1") (pintype "passive"))
      (node (ref "U1") (pin "10") (pinfunction "LSS_2_10") (pintype "passive"))
      (node (ref "U1") (pin "12") (pinfunction "LSS_12") (pintype "passive"))
    )
    (net (code "75") (name "Net-(U1-VCP)") (class "Default")
      (node (ref "C3") (pin "1") (pinfunction "1_1") (pintype "passive"))
      (node (ref "U1") (pin "19") (pinfunction "VCP_19") (pintype "output"))
    )
    (net (code "76") (name "Net-(U1-VG)") (class "Default")
      (node (ref "C1") (pin "1") (pinfunction "1_1") (pintype "passive"))
      (node (ref "U1") (pin "14") (pinfunction "VG_14") (pintype "power_in"))
    )
    (net (code "77") (name "Net-(U2A-VCAP_1)") (class "Default")
      (node (ref "C23") (pin "2") (pinfunction "2_2") (pintype "passive"))
      (node (ref "U2") (pin "48") (pinfunction "VCAP_1_48") (pintype "power_in"))
    )
    (net (code "78") (name "Net-(U2B-VCAP_2)") (class "Default")
      (node (ref "C19") (pin "1") (pinfunction "1_1") (pintype "passive"))
      (node (ref "U2") (pin "73") (pinfunction "VCAP_2_73") (pintype "power_in"))
    )
    (net (code "79") (name "Net-(U3-CP1)") (class "Default")
      (node (ref "C30") (pin "2") (pinfunction "2_2") (pintype "passive"))
      (node (ref "U3") (pin "20") (pinfunction "CP1_20") (pintype "passive"))
    )
    (net (code "80") (name "Net-(U3-CP2)") (class "Default")
      (node (ref "C30") (pin "1") (pinfunction "1_1") (pintype "passive"))
      (node (ref "U3") (pin "21") (pinfunction "CP2_21") (pintype "passive"))
    )
    (net (code "81") (name "Net-(U3-LSS)") (class "Default")
      (node (ref "R36") (pin "2") (pinfunction "2_2") (pintype "passive"))
      (node (ref "R7") (pin "1") (pinfunction "1_1") (pintype "passive"))
      (node (ref "U3") (pin "10") (pinfunction "LSS_2_10") (pintype "passive"))
      (node (ref "U3") (pin "12") (pinfunction "LSS_12") (pintype "passive"))
    )
    (net (code "82") (name "Net-(U3-VCP)") (class "Default")
      (node (ref "C31") (pin "1") (pinfunction "1_1") (pintype "passive"))
      (node (ref "U3") (pin "19") (pinfunction "VCP_19") (pintype "output"))
    )
    (net (code "83") (name "Net-(U3-VG)") (class "Default")
      (node (ref "C13") (pin "1") (pinfunction "1_1") (pintype "passive"))
      (node (ref "U3") (pin "14") (pinfunction "VG_14") (pintype "power_in"))
    )
    (net (code "84") (name "Net-(U4-BST)") (class "Default")
      (node (ref "C39") (pin "2") (pinfunction "2_2") (pintype "passive"))
      (node (ref "U4") (pin "6") (pinfunction "BST_6") (pintype "bidirectional"))
    )
    (net (code "85") (name "VCC") (class "Default")
      (node (ref "C10") (pin "+") (pinfunction "+_+") (pintype "passive"))
      (node (ref "C17") (pin "2") (pinfunction "2_2") (pintype "passive"))
      (node (ref "C18") (pin "2") (pinfunction "2_2") (pintype "passive"))
      (node (ref "C3") (pin "2") (pinfunction "2_2") (pintype "passive"))
      (node (ref "C31") (pin "2") (pinfunction "2_2") (pintype "passive"))
      (node (ref "C32") (pin "2") (pinfunction "2_2") (pintype "passive"))
      (node (ref "C33") (pin "2") (pinfunction "2_2") (pintype "passive"))
      (node (ref "C4") (pin "+") (pinfunction "+_+") (pintype "passive"))
      (node (ref "C40") (pin "2") (pinfunction "2_2") (pintype "passive"))
      (node (ref "C41") (pin "2") (pinfunction "2_2") (pintype "passive"))
      (node (ref "D1") (pin "C") (pinfunction "C_C") (pintype "passive"))
      (node (ref "JP1") (pin "2") (pinfunction "2_2") (pintype "passive"))
      (node (ref "U1") (pin "23") (pinfunction "VIN_2_23") (pintype "power_in"))
      (node (ref "U1") (pin "25") (pinfunction "VIN_25") (pintype "power_in"))
      (node (ref "U3") (pin "23") (pinfunction "VIN_2_23") (pintype "power_in"))
      (node (ref "U3") (pin "25") (pinfunction "VIN_25") (pintype "power_in"))
      (node (ref "U4") (pin "2") (pinfunction "EN_2") (pintype "bidirectional"))
      (node (ref "U4") (pin "3") (pinfunction "VIN_3") (pintype "bidirectional"))
    )
    (net (code "86") (name "unconnected-(U$3-INT1-PadP$4)") (class "Default")
      (node (ref "U$3") (pin "P$4") (pinfunction "INT1_P$4") (pintype "bidirectional"))
    )
    (net (code "87") (name "unconnected-(U$3-INT2-PadP$9)") (class "Default")
      (node (ref "U$3") (pin "P$9") (pinfunction "INT2_P$9") (pintype "bidirectional"))
    )
    (net (code "88") (name "unconnected-(U$3-NC1-PadP$10)") (class "Default")
      (node (ref "U$3") (pin "P$10") (pinfunction "NC1_P$10") (pintype "bidirectional"))
    )
    (net (code "89") (name "unconnected-(U$3-NC2-PadP$11)") (class "Default")
      (node (ref "U$3") (pin "P$11") (pinfunction "NC2_P$11") (pintype "bidirectional"))
    )
    (net (code "90") (name "unconnected-(U1-NFAULT-Pad1)") (class "Default")
      (node (ref "U1") (pin "1") (pinfunction "NFAULT_1") (pintype "output"))
    )
    (net (code "91") (name "unconnected-(U1-SOA-Pad15)") (class "Default")
      (node (ref "U1") (pin "15") (pinfunction "SOA_15") (pintype "output"))
    )
    (net (code "92") (name "unconnected-(U1-SOB-Pad16)") (class "Default")
      (node (ref "U1") (pin "16") (pinfunction "SOB_16") (pintype "output"))
    )
    (net (code "93") (name "unconnected-(U1-SOC-Pad17)") (class "Default")
      (node (ref "U1") (pin "17") (pinfunction "SOC_17") (pintype "output"))
    )
    (net (code "94") (name "unconnected-(U2A-PB2-Pad36)") (class "Default")
      (node (ref "U2") (pin "36") (pinfunction "PB2_36") (pintype "bidirectional"))
    )
    (net (code "95") (name "unconnected-(U2A-PB10-Pad46)") (class "Default")
      (node (ref "U2") (pin "46") (pinfunction "PB10_46") (pintype "bidirectional"))
    )
    (net (code "96") (name "unconnected-(U2A-PB11-Pad47)") (class "Default")
      (node (ref "U2") (pin "47") (pinfunction "PB11_47") (pintype "bidirectional"))
    )
    (net (code "97") (name "unconnected-(U2A-PC0-Pad15)") (class "Default")
      (node (ref "U2") (pin "15") (pinfunction "PC0_15") (pintype "bidirectional"))
    )
    (net (code "98") (name "unconnected-(U2A-PC1-Pad16)") (class "Default")
      (node (ref "U2") (pin "16") (pinfunction "PC1_16") (pintype "bidirectional"))
    )
    (net (code "99") (name "unconnected-(U2A-PC13-Pad7)") (class "Default")
      (node (ref "U2") (pin "7") (pinfunction "PC13_7") (pintype "bidirectional"))
    )
    (net (code "100") (name "unconnected-(U2A-PC14-Pad8)") (class "Default")
      (node (ref "U2") (pin "8") (pinfunction "PC14_8") (pintype "bidirectional"))
    )
    (net (code "101") (name "unconnected-(U2A-PE5-Pad4)") (class "Default")
      (node (ref "U2") (pin "4") (pinfunction "PE5_4") (pintype "bidirectional"))
    )
    (net (code "102") (name "unconnected-(U2A-PE6-Pad5)") (class "Default")
      (node (ref "U2") (pin "5") (pinfunction "PE6_5") (pintype "bidirectional"))
    )
    (net (code "103") (name "unconnected-(U2A-PE7-Pad37)") (class "Default")
      (node (ref "U2") (pin "37") (pinfunction "PE7_37") (pintype "bidirectional"))
    )
    (net (code "104") (name "unconnected-(U2A-PE8-Pad38)") (class "Default")
      (node (ref "U2") (pin "38") (pinfunction "PE8_38") (pintype "bidirectional"))
    )
    (net (code "105") (name "unconnected-(U2A-PE9-Pad39)") (class "Default")
      (node (ref "U2") (pin "39") (pinfunction "PE9_39") (pintype "bidirectional"))
    )
    (net (code "106") (name "unconnected-(U2A-PE10-Pad40)") (class "Default")
      (node (ref "U2") (pin "40") (pinfunction "PE10_40") (pintype "bidirectional"))
    )
    (net (code "107") (name "unconnected-(U2A-PE11-Pad41)") (class "Default")
      (node (ref "U2") (pin "41") (pinfunction "PE11_41") (pintype "bidirectional"))
    )
    (net (code "108") (name "unconnected-(U2A-PE12-Pad42)") (class "Default")
      (node (ref "U2") (pin "42") (pinfunction "PE12_42") (pintype "bidirectional"))
    )
    (net (code "109") (name "unconnected-(U2A-PE13-Pad43)") (class "Default")
      (node (ref "U2") (pin "43") (pinfunction "PE13_43") (pintype "bidirectional"))
    )
    (net (code "110") (name "unconnected-(U2A-PE14-Pad44)") (class "Default")
      (node (ref "U2") (pin "44") (pinfunction "PE14_44") (pintype "bidirectional"))
    )
    (net (code "111") (name "unconnected-(U2A-PE15-Pad45)") (class "Default")
      (node (ref "U2") (pin "45") (pinfunction "PE15_45") (pintype "bidirectional"))
    )
    (net (code "112") (name "unconnected-(U2B-PA15-Pad77)") (class "Default")
      (node (ref "U2") (pin "77") (pinfunction "PA15_77") (pintype "bidirectional"))
    )
    (net (code "113") (name "unconnected-(U2B-PB3-Pad89)") (class "Default")
      (node (ref "U2") (pin "89") (pinfunction "PB3_89") (pintype "bidirectional"))
    )
    (net (code "114") (name "unconnected-(U2B-PB4-Pad90)") (class "Default")
      (node (ref "U2") (pin "90") (pinfunction "PB4_90") (pintype "bidirectional"))
    )
    (net (code "115") (name "unconnected-(U2B-PB5-Pad91)") (class "Default")
      (node (ref "U2") (pin "91") (pinfunction "PB5_91") (pintype "bidirectional"))
    )
    (net (code "116") (name "unconnected-(U2B-PB12-Pad51)") (class "Default")
      (node (ref "U2") (pin "51") (pinfunction "PB12_51") (pintype "bidirectional"))
    )
    (net (code "117") (name "unconnected-(U2B-PB13-Pad52)") (class "Default")
      (node (ref "U2") (pin "52") (pinfunction "PB13_52") (pintype "bidirectional"))
    )
    (net (code "118") (name "unconnected-(U2B-PB14-Pad53)") (class "Default")
      (node (ref "U2") (pin "53") (pinfunction "PB14_53") (pintype "bidirectional"))
    )
    (net (code "119") (name "unconnected-(U2B-PC6-Pad63)") (class "Default")
      (node (ref "U2") (pin "63") (pinfunction "PC6_63") (pintype "bidirectional"))
    )
    (net (code "120") (name "unconnected-(U2B-PC10-Pad78)") (class "Default")
      (node (ref "U2") (pin "78") (pinfunction "PC10_78") (pintype "bidirectional"))
    )
    (net (code "121") (name "unconnected-(U2B-PC11-Pad79)") (class "Default")
      (node (ref "U2") (pin "79") (pinfunction "PC11_79") (pintype "bidirectional"))
    )
    (net (code "122") (name "unconnected-(U2B-PC12-Pad80)") (class "Default")
      (node (ref "U2") (pin "80") (pinfunction "PC12_80") (pintype "bidirectional"))
    )
    (net (code "123") (name "unconnected-(U2B-PD0-Pad81)") (class "Default")
      (node (ref "U2") (pin "81") (pinfunction "PD0_81") (pintype "bidirectional"))
    )
    (net (code "124") (name "unconnected-(U2B-PD5-Pad86)") (class "Default")
      (node (ref "U2") (pin "86") (pinfunction "PD5_86") (pintype "bidirectional"))
    )
    (net (code "125") (name "unconnected-(U2B-PD6-Pad87)") (class "Default")
      (node (ref "U2") (pin "87") (pinfunction "PD6_87") (pintype "bidirectional"))
    )
    (net (code "126") (name "unconnected-(U2B-PD7-Pad88)") (class "Default")
      (node (ref "U2") (pin "88") (pinfunction "PD7_88") (pintype "bidirectional"))
    )
    (net (code "127") (name "unconnected-(U2B-PD8-Pad55)") (class "Default")
      (node (ref "U2") (pin "55") (pinfunction "PD8_55") (pintype "bidirectional"))
    )
    (net (code "128") (name "unconnected-(U2B-PD9-Pad56)") (class "Default")
      (node (ref "U2") (pin "56") (pinfunction "PD9_56") (pintype "bidirectional"))
    )
    (net (code "129") (name "unconnected-(U2B-PD10-Pad57)") (class "Default")
      (node (ref "U2") (pin "57") (pinfunction "PD10_57") (pintype "bidirectional"))
    )
    (net (code "130") (name "unconnected-(U2B-PD11-Pad58)") (class "Default")
      (node (ref "U2") (pin "58") (pinfunction "PD11_58") (pintype "bidirectional"))
    )
    (net (code "131") (name "unconnected-(U2B-PD12-Pad59)") (class "Default")
      (node (ref "U2") (pin "59") (pinfunction "PD12_59") (pintype "bidirectional"))
    )
    (net (code "132") (name "unconnected-(U3-NFAULT-Pad1)") (class "Default")
      (node (ref "U3") (pin "1") (pinfunction "NFAULT_1") (pintype "output"))
    )
    (net (code "133") (name "unconnected-(U3-SOA-Pad15)") (class "Default")
      (node (ref "U3") (pin "15") (pinfunction "SOA_15") (pintype "output"))
    )
    (net (code "134") (name "unconnected-(U3-SOB-Pad16)") (class "Default")
      (node (ref "U3") (pin "16") (pinfunction "SOB_16") (pintype "output"))
    )
    (net (code "135") (name "unconnected-(U3-SOC-Pad17)") (class "Default")
      (node (ref "U3") (pin "17") (pinfunction "SOC_17") (pintype "output"))
    )
    (net (code "136") (name "unconnected-(USB-PadID)") (class "Default")
      (node (ref "USB") (pin "ID") (pinfunction "ID_ID") (pintype "bidirectional"))
    )
    (net (code "137") (name "unconnected-(USER-Pad3)") (class "Default")
      (node (ref "USER") (pin "3") (pinfunction "3_3") (pintype "passive"))
    )
  )
)
